# Logic_IO_Unit_V2.net
KiCad netlist of a schematic drawn in Altium Designer
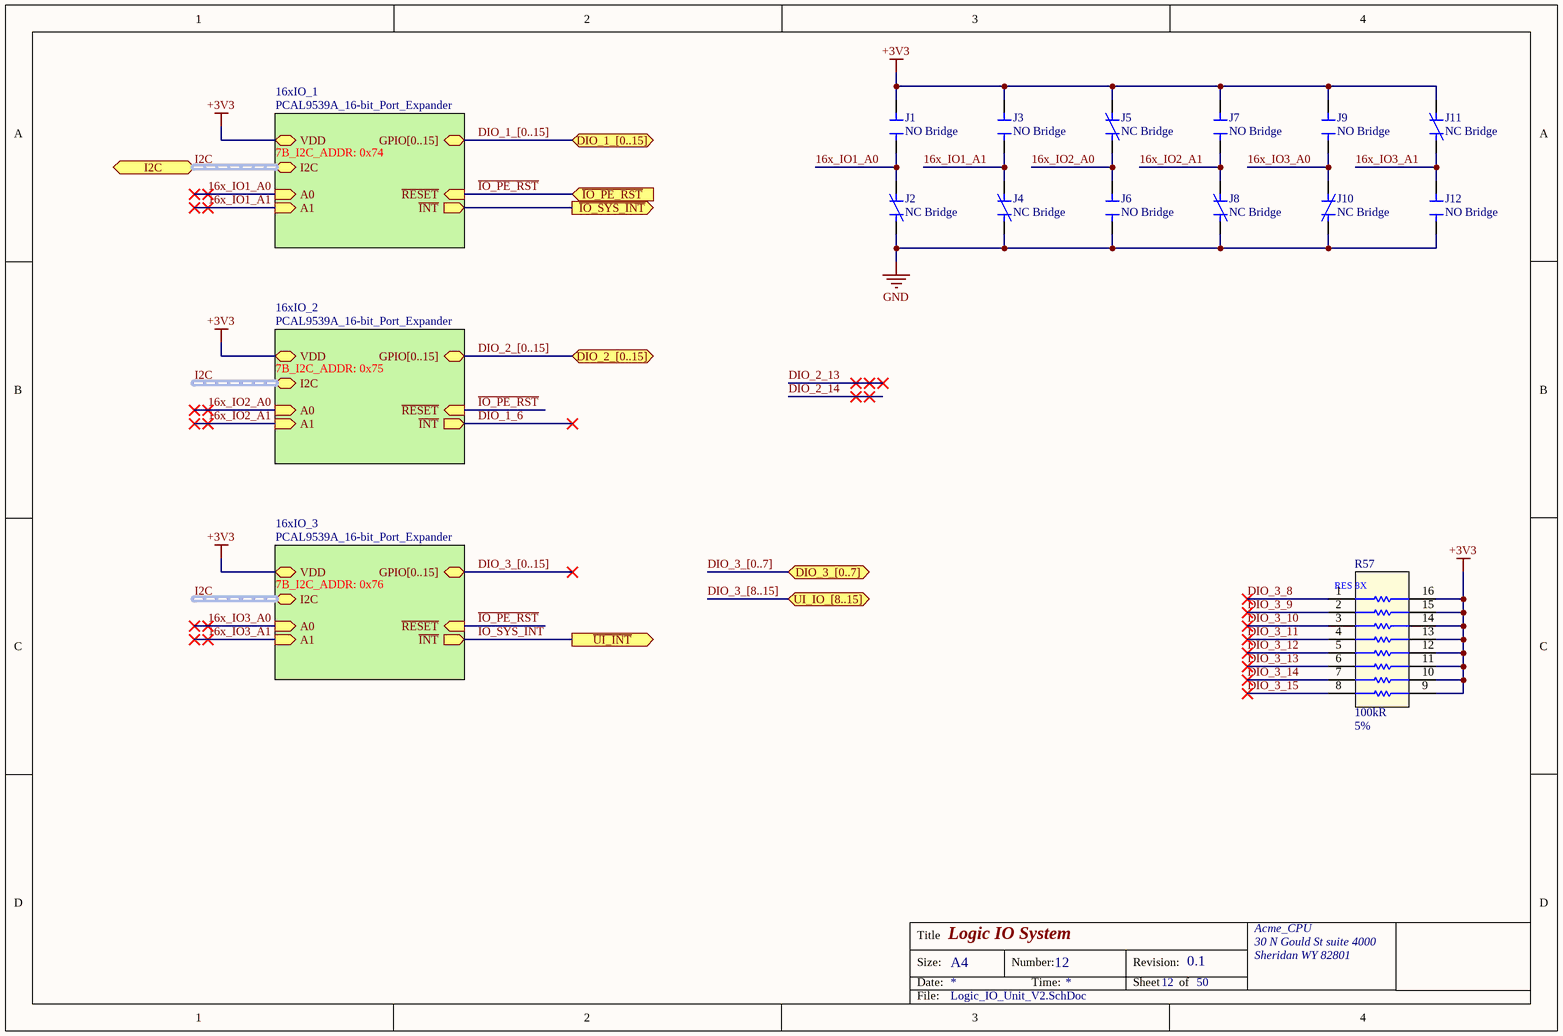
[diagram p0: Logic_IO_Unit_V2.SchDoc]

(export (version "E")
  (design (tool "Eeschema 10.0.6"))
  (components
    (comp (ref "J1")
      (value "NO Bridge")
      (footprint "NO_SolderBridge_0603")
      (description "NO PCB Bridge (May be closed by a solder blob)")
      (libsource (lib "BLDC_Motor_Driver") (part "NO Bridge"))
    )
    (comp (ref "J2")
      (value "NC Bridge")
      (footprint "NC_SolderBridge_0603")
      (description "NC PCB Bridge (May be opened by cutting the copper trace)")
      (libsource (lib "BLDC_Motor_Driver") (part "NC Bridge"))
    )
    (comp (ref "J3")
      (value "NO Bridge")
      (footprint "NO_SolderBridge_0603")
      (description "NO PCB Bridge (May be closed by a solder blob)")
      (libsource (lib "BLDC_Motor_Driver") (part "NO Bridge"))
    )
    (comp (ref "J4")
      (value "NC Bridge")
      (footprint "NC_SolderBridge_0603")
      (description "NC PCB Bridge (May be opened by cutting the copper trace)")
      (libsource (lib "BLDC_Motor_Driver") (part "NC Bridge"))
    )
    (comp (ref "J5")
      (value "NC Bridge")
      (footprint "NC_SolderBridge_0603")
      (description "NC PCB Bridge (May be opened by cutting the copper trace)")
      (libsource (lib "BLDC_Motor_Driver") (part "NC Bridge"))
    )
    (comp (ref "J6")
      (value "NO Bridge")
      (footprint "NO_SolderBridge_0603")
      (description "NO PCB Bridge (May be closed by a solder blob)")
      (libsource (lib "BLDC_Motor_Driver") (part "NO Bridge"))
    )
    (comp (ref "J7")
      (value "NO Bridge")
      (footprint "NO_SolderBridge_0603")
      (description "NO PCB Bridge (May be closed by a solder blob)")
      (libsource (lib "BLDC_Motor_Driver") (part "NO Bridge"))
    )
    (comp (ref "J8")
      (value "NC Bridge")
      (footprint "NC_SolderBridge_0603")
      (description "NC PCB Bridge (May be opened by cutting the copper trace)")
      (libsource (lib "BLDC_Motor_Driver") (part "NC Bridge"))
    )
    (comp (ref "J9")
      (value "NO Bridge")
      (footprint "NO_SolderBridge_0603")
      (description "NO PCB Bridge (May be closed by a solder blob)")
      (libsource (lib "BLDC_Motor_Driver") (part "NO Bridge"))
    )
    (comp (ref "J10")
      (value "NC Bridge")
      (footprint "NC_SolderBridge_0603")
      (description "NC PCB Bridge (May be opened by cutting the copper trace)")
      (libsource (lib "BLDC_Motor_Driver") (part "NC Bridge"))
    )
    (comp (ref "J11")
      (value "NC Bridge")
      (footprint "NC_SolderBridge_0603")
      (description "NC PCB Bridge (May be opened by cutting the copper trace)")
      (libsource (lib "BLDC_Motor_Driver") (part "NC Bridge"))
    )
    (comp (ref "J12")
      (value "NO Bridge")
      (footprint "NO_SolderBridge_0603")
      (description "NO PCB Bridge (May be closed by a solder blob)")
      (libsource (lib "BLDC_Motor_Driver") (part "NO Bridge"))
    )
    (comp (ref "R57")
      (value "RES ARRAY 8 RES 100K OHM 1606")
      (footprint "YAG_YC248")
      (fields
        (field (name "MANUFACTURER") "Yageo")
        (field (name "MANUFACTURER PART NUMBER") "YC248-JR-07100KL")
        (field (name "RESISTANCE") "100kR")
        (field (name "TOLERANCE") "5%")
      )
      (libsource (lib "resistors_smd") (part "RES ARRAY 8 RES 100K OHM 1606"))
    )
  )
  (nets
    (net (code "39") (name "+3V3") (class "Default")
      (node (ref "J1") (pin "2") (pinfunction "2_2") (pintype "passive"))
      (node (ref "J11") (pin "2") (pinfunction "2_2") (pintype "passive"))
      (node (ref "J3") (pin "2") (pinfunction "2_2") (pintype "passive"))
      (node (ref "J5") (pin "2") (pinfunction "2_2") (pintype "passive"))
      (node (ref "J7") (pin "2") (pinfunction "2_2") (pintype "passive"))
      (node (ref "J9") (pin "2") (pinfunction "2_2") (pintype "passive"))
      (node (ref "R57") (pin "10") (pinfunction "110_10") (pintype "passive"))
      (node (ref "R57") (pin "11") (pinfunction "111_11") (pintype "passive"))
      (node (ref "R57") (pin "12") (pinfunction "112_12") (pintype "passive"))
      (node (ref "R57") (pin "13") (pinfunction "113_13") (pintype "passive"))
      (node (ref "R57") (pin "14") (pinfunction "114_14") (pintype "passive"))
      (node (ref "R57") (pin "15") (pinfunction "115_15") (pintype "passive"))
      (node (ref "R57") (pin "16") (pinfunction "116_16") (pintype "passive"))
      (node (ref "R57") (pin "9") (pinfunction "19_9") (pintype "passive"))
    )
    (net (code "40") (name "/16x_IO1_A0") (class "Default")
      (node (ref "J1") (pin "1") (pinfunction "1_1") (pintype "passive"))
      (node (ref "J2") (pin "2") (pinfunction "2_2") (pintype "passive"))
    )
    (net (code "41") (name "/16x_IO1_A1") (class "Default")
      (node (ref "J3") (pin "1") (pinfunction "1_1") (pintype "passive"))
      (node (ref "J4") (pin "2") (pinfunction "2_2") (pintype "passive"))
    )
    (net (code "42") (name "/16x_IO2_A0") (class "Default")
      (node (ref "J5") (pin "1") (pinfunction "1_1") (pintype "passive"))
      (node (ref "J6") (pin "2") (pinfunction "2_2") (pintype "passive"))
    )
    (net (code "43") (name "/16x_IO2_A1") (class "Default")
      (node (ref "J7") (pin "1") (pinfunction "1_1") (pintype "passive"))
      (node (ref "J8") (pin "2") (pinfunction "2_2") (pintype "passive"))
    )
    (net (code "44") (name "/16x_IO3_A0") (class "Default")
      (node (ref "J10") (pin "2") (pinfunction "2_2") (pintype "passive"))
      (node (ref "J9") (pin "1") (pinfunction "1_1") (pintype "passive"))
    )
    (net (code "45") (name "/16x_IO3_A1") (class "Default")
      (node (ref "J11") (pin "1") (pinfunction "1_1") (pintype "passive"))
      (node (ref "J12") (pin "2") (pinfunction "2_2") (pintype "passive"))
    )
    (net (code "57") (name "/DIO_3_8") (class "Default")
      (node (ref "R57") (pin "1") (pinfunction "11_1") (pintype "passive+no_connect"))
    )
    (net (code "58") (name "/DIO_3_9") (class "Default")
      (node (ref "R57") (pin "2") (pinfunction "12_2") (pintype "passive+no_connect"))
    )
    (net (code "59") (name "/DIO_3_10") (class "Default")
      (node (ref "R57") (pin "3") (pinfunction "13_3") (pintype "passive+no_connect"))
    )
    (net (code "60") (name "/DIO_3_11") (class "Default")
      (node (ref "R57") (pin "4") (pinfunction "14_4") (pintype "passive+no_connect"))
    )
    (net (code "61") (name "/DIO_3_12") (class "Default")
      (node (ref "R57") (pin "5") (pinfunction "15_5") (pintype "passive+no_connect"))
    )
    (net (code "62") (name "/DIO_3_13") (class "Default")
      (node (ref "R57") (pin "6") (pinfunction "16_6") (pintype "passive+no_connect"))
    )
    (net (code "63") (name "/DIO_3_14") (class "Default")
      (node (ref "R57") (pin "7") (pinfunction "17_7") (pintype "passive+no_connect"))
    )
    (net (code "64") (name "/DIO_3_15") (class "Default")
      (node (ref "R57") (pin "8") (pinfunction "18_8") (pintype "passive+no_connect"))
    )
    (net (code "71") (name "GND") (class "Default")
      (node (ref "J10") (pin "1") (pinfunction "1_1") (pintype "passive"))
      (node (ref "J12") (pin "1") (pinfunction "1_1") (pintype "passive"))
      (node (ref "J2") (pin "1") (pinfunction "1_1") (pintype "passive"))
      (node (ref "J4") (pin "1") (pinfunction "1_1") (pintype "passive"))
      (node (ref "J6") (pin "1") (pinfunction "1_1") (pintype "passive"))
      (node (ref "J8") (pin "1") (pinfunction "1_1") (pintype "passive"))
    )
  )
)
